# adapter.net
KiCad netlist of a schematic drawn in EAGLE
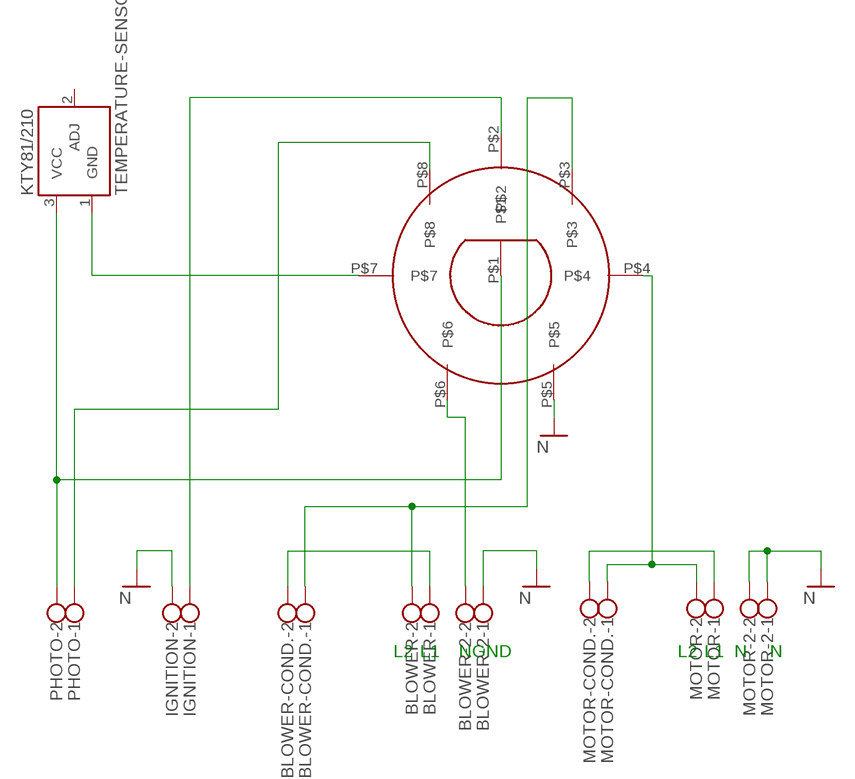
[diagram p0: schematic, sheet 1]

(export (version "E")
  (design (tool "Eeschema 10.0.6"))
  (components
    (comp (ref "BLOWER")
      (value "W237-102")
      (footprint "eagle-import:W237-102")
      (fields (field (name "MPN") "237-102"))
      (libsource (lib "eagle-import") (part "W237-102"))
    )
    (comp (ref "BLOWER-2")
      (value "W237-102")
      (footprint "eagle-import:W237-102")
      (fields (field (name "MPN") "237-102"))
      (libsource (lib "eagle-import") (part "W237-102"))
    )
    (comp (ref "BLOWER-COND.")
      (value "W237-102")
      (footprint "eagle-import:W237-102")
      (fields (field (name "MPN") "237-102"))
      (libsource (lib "eagle-import") (part "W237-102"))
    )
    (comp (ref "IGNITION")
      (value "W237-102")
      (footprint "eagle-import:W237-102")
      (fields (field (name "MPN") "237-102"))
      (libsource (lib "eagle-import") (part "W237-102"))
    )
    (comp (ref "KTY81/210")
      (value "TEMPERATURE-SENSOR")
      (footprint "eagle-import:TO-92")
      (libsource (lib "eagle-import") (part "TEMPERATURE-SENSOR"))
    )
    (comp (ref "MOTOR")
      (value "W237-102")
      (footprint "eagle-import:W237-102")
      (fields (field (name "MPN") "237-102"))
      (libsource (lib "eagle-import") (part "W237-102"))
    )
    (comp (ref "MOTOR-2")
      (value "W237-102")
      (footprint "eagle-import:W237-102")
      (fields (field (name "MPN") "237-102"))
      (libsource (lib "eagle-import") (part "W237-102"))
    )
    (comp (ref "MOTOR-COND.")
      (value "W237-102")
      (footprint "eagle-import:W237-102")
      (fields (field (name "MPN") "237-102"))
      (libsource (lib "eagle-import") (part "W237-102"))
    )
    (comp (ref "PHOTO")
      (value "W237-102")
      (footprint "eagle-import:W237-102")
      (fields (field (name "MPN") "237-102"))
      (libsource (lib "eagle-import") (part "W237-102"))
    )
    (comp (ref "U$1")
      (value "PX0959/P")
      (footprint "eagle-import:PX0959_P")
      (libsource (lib "eagle-import") (part "PX0959/P"))
    )
  )
  (nets
    (net (code "1") (name "N") (class "Default")
      (node (ref "BLOWER-2") (pin "1") (pinfunction "KL_1") (pintype "passive"))
      (node (ref "IGNITION") (pin "2") (pinfunction "KL_2") (pintype "passive"))
      (node (ref "MOTOR-2") (pin "1") (pinfunction "KL_1") (pintype "passive"))
      (node (ref "MOTOR-2") (pin "2") (pinfunction "KL_2") (pintype "passive"))
      (node (ref "U$1") (pin "P$5") (pinfunction "P$5_P$5") (pintype "bidirectional"))
    )
    (net (code "2") (name "Net-(BLOWER-2B-KL)") (class "Default")
      (node (ref "BLOWER-2") (pin "2") (pinfunction "KL_2") (pintype "passive"))
      (node (ref "U$1") (pin "P$6") (pinfunction "P$6_P$6") (pintype "bidirectional"))
    )
    (net (code "3") (name "Net-(BLOWER-COND.A-KL)") (class "Default")
      (node (ref "BLOWER") (pin "2") (pinfunction "KL_2") (pintype "passive"))
      (node (ref "BLOWER-COND.") (pin "1") (pinfunction "KL_1") (pintype "passive"))
      (node (ref "U$1") (pin "P$3") (pinfunction "P$3_P$3") (pintype "bidirectional"))
    )
    (net (code "4") (name "Net-(BLOWER-COND.B-KL)") (class "Default")
      (node (ref "BLOWER") (pin "1") (pinfunction "KL_1") (pintype "passive"))
      (node (ref "BLOWER-COND.") (pin "2") (pinfunction "KL_2") (pintype "passive"))
    )
    (net (code "5") (name "Net-(IGNITIONA-KL)") (class "Default")
      (node (ref "IGNITION") (pin "1") (pinfunction "KL_1") (pintype "passive"))
      (node (ref "U$1") (pin "P$2") (pinfunction "P$2_P$2") (pintype "bidirectional"))
    )
    (net (code "6") (name "Net-(KTY81/210-GND)") (class "Default")
      (node (ref "KTY81/210") (pin "1") (pinfunction "GND_1") (pintype "bidirectional"))
      (node (ref "U$1") (pin "P$7") (pinfunction "P$7_P$7") (pintype "bidirectional"))
    )
    (net (code "7") (name "Net-(KTY81/210-VCC)") (class "Default")
      (node (ref "KTY81/210") (pin "3") (pinfunction "VCC_3") (pintype "bidirectional"))
      (node (ref "PHOTO") (pin "2") (pinfunction "KL_2") (pintype "passive"))
      (node (ref "U$1") (pin "P$1") (pinfunction "P$1_P$1") (pintype "bidirectional"))
    )
    (net (code "8") (name "Net-(MOTOR-COND.A-KL)") (class "Default")
      (node (ref "MOTOR") (pin "2") (pinfunction "KL_2") (pintype "passive"))
      (node (ref "MOTOR-COND.") (pin "1") (pinfunction "KL_1") (pintype "passive"))
      (node (ref "U$1") (pin "P$4") (pinfunction "P$4_P$4") (pintype "bidirectional"))
    )
    (net (code "9") (name "Net-(MOTOR-COND.B-KL)") (class "Default")
      (node (ref "MOTOR") (pin "1") (pinfunction "KL_1") (pintype "passive"))
      (node (ref "MOTOR-COND.") (pin "2") (pinfunction "KL_2") (pintype "passive"))
    )
    (net (code "10") (name "Net-(PHOTOA-KL)") (class "Default")
      (node (ref "PHOTO") (pin "1") (pinfunction "KL_1") (pintype "passive"))
      (node (ref "U$1") (pin "P$8") (pinfunction "P$8_P$8") (pintype "bidirectional"))
    )
    (net (code "11") (name "unconnected-(KTY81/210-ADJ-Pad2)") (class "Default")
      (node (ref "KTY81/210") (pin "2") (pinfunction "ADJ_2") (pintype "bidirectional"))
    )
  )
)
